# DigitalHourglass.net
KiCad netlist of a schematic drawn in EAGLE
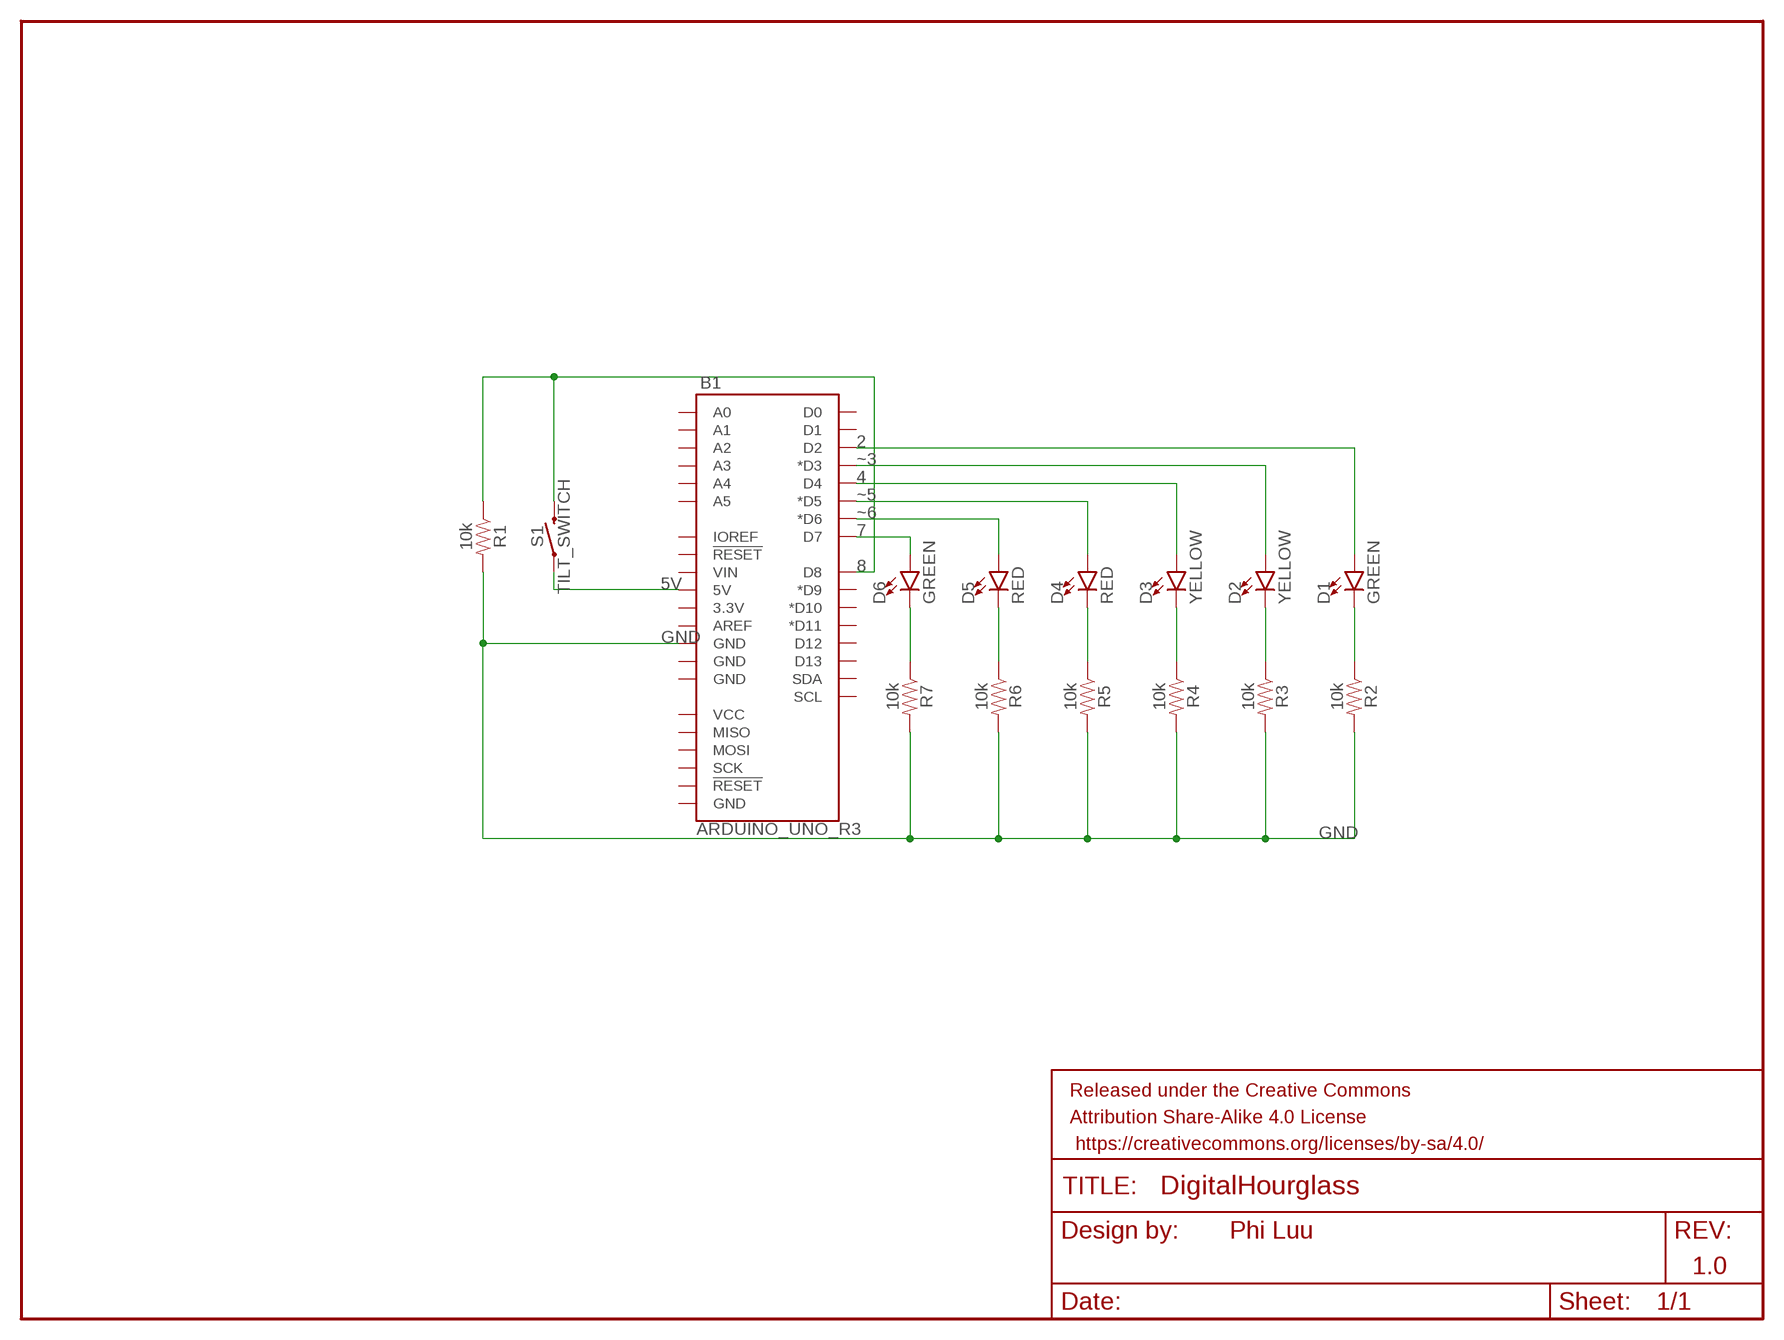
[diagram p0: schematic, sheet 1]

(export (version "E")
  (design (tool "Eeschema 10.0.6"))
  (components
    (comp (ref "B1")
      (value "ARDUINO_UNO_R3")
      (footprint "eagle-import:ARDUINO_R3")
      (libsource (lib "eagle-import") (part "ARDUINO_UNO_R3"))
    )
    (comp (ref "D1")
      (value "GREEN")
      (footprint "eagle-import:LED_5MM")
      (libsource (lib "eagle-import") (part "LED5MM"))
    )
    (comp (ref "D2")
      (value "YELLOW")
      (footprint "eagle-import:LED_5MM")
      (libsource (lib "eagle-import") (part "LED5MM"))
    )
    (comp (ref "D3")
      (value "YELLOW")
      (footprint "eagle-import:LED_5MM")
      (libsource (lib "eagle-import") (part "LED5MM"))
    )
    (comp (ref "D4")
      (value "RED")
      (footprint "eagle-import:LED_5MM")
      (libsource (lib "eagle-import") (part "LED5MM"))
    )
    (comp (ref "D5")
      (value "RED")
      (footprint "eagle-import:LED_5MM")
      (libsource (lib "eagle-import") (part "LED5MM"))
    )
    (comp (ref "D6")
      (value "GREEN")
      (footprint "eagle-import:LED_5MM")
      (libsource (lib "eagle-import") (part "LED5MM"))
    )
    (comp (ref "FRAME1")
      (value "FRAME-LETTER")
      (footprint "eagle-import:CREATIVE_COMMONS")
      (libsource (lib "eagle-import") (part "FRAME-LETTER"))
    )
    (comp (ref "R1")
      (value "10k")
      (footprint "eagle-import:AXIAL-0.3")
      (libsource (lib "eagle-import") (part "10KOHM-HORIZ-1/4W-5%"))
    )
    (comp (ref "R2")
      (value "10k")
      (footprint "eagle-import:AXIAL-0.3")
      (libsource (lib "eagle-import") (part "10KOHM-HORIZ-1/4W-5%"))
    )
    (comp (ref "R3")
      (value "10k")
      (footprint "eagle-import:AXIAL-0.3")
      (libsource (lib "eagle-import") (part "10KOHM-HORIZ-1/4W-5%"))
    )
    (comp (ref "R4")
      (value "10k")
      (footprint "eagle-import:AXIAL-0.3")
      (libsource (lib "eagle-import") (part "10KOHM-HORIZ-1/4W-5%"))
    )
    (comp (ref "R5")
      (value "10k")
      (footprint "eagle-import:AXIAL-0.3")
      (libsource (lib "eagle-import") (part "10KOHM-HORIZ-1/4W-5%"))
    )
    (comp (ref "R6")
      (value "10k")
      (footprint "eagle-import:AXIAL-0.3")
      (libsource (lib "eagle-import") (part "10KOHM-HORIZ-1/4W-5%"))
    )
    (comp (ref "R7")
      (value "10k")
      (footprint "eagle-import:AXIAL-0.3")
      (libsource (lib "eagle-import") (part "10KOHM-HORIZ-1/4W-5%"))
    )
    (comp (ref "S1")
      (value "TILT_SWITCH")
      (footprint "eagle-import:TACTILE_SWITCH_PTH_6.0MM")
      (libsource (lib "eagle-import") (part "MOMENTARY-SWITCH-SPST-PTH-6.0MM"))
    )
  )
  (nets
    (net (code "1") (name "/2") (class "Default")
      (node (ref "B1") (pin "D2") (pinfunction "D2_D2") (pintype "bidirectional"))
      (node (ref "D1") (pin "A") (pinfunction "A_A") (pintype "passive"))
    )
    (net (code "2") (name "/4") (class "Default")
      (node (ref "B1") (pin "D4") (pinfunction "D4_D4") (pintype "bidirectional"))
      (node (ref "D3") (pin "A") (pinfunction "A_A") (pintype "passive"))
    )
    (net (code "3") (name "/5V") (class "Default")
      (node (ref "B1") (pin "5V") (pinfunction "5V_5V") (pintype "bidirectional"))
      (node (ref "S1") (pin "1") (pinfunction "1_1") (pintype "passive"))
    )
    (net (code "4") (name "/7") (class "Default")
      (node (ref "B1") (pin "D7") (pinfunction "D7_D7") (pintype "bidirectional"))
      (node (ref "D6") (pin "A") (pinfunction "A_A") (pintype "passive"))
    )
    (net (code "5") (name "/8") (class "Default")
      (node (ref "B1") (pin "D8") (pinfunction "D8_D8") (pintype "bidirectional"))
      (node (ref "R1") (pin "P$1") (pinfunction "1_P$1") (pintype "passive"))
      (node (ref "S1") (pin "3") (pinfunction "2_3") (pintype "passive"))
    )
    (net (code "6") (name "/GND") (class "Default")
      (node (ref "B1") (pin "GND@4") (pinfunction "GND_GND@4") (pintype "bidirectional"))
      (node (ref "R1") (pin "P$2") (pinfunction "2_P$2") (pintype "passive"))
      (node (ref "R2") (pin "P$2") (pinfunction "2_P$2") (pintype "passive"))
      (node (ref "R3") (pin "P$2") (pinfunction "2_P$2") (pintype "passive"))
      (node (ref "R4") (pin "P$2") (pinfunction "2_P$2") (pintype "passive"))
      (node (ref "R5") (pin "P$2") (pinfunction "2_P$2") (pintype "passive"))
      (node (ref "R6") (pin "P$2") (pinfunction "2_P$2") (pintype "passive"))
      (node (ref "R7") (pin "P$2") (pinfunction "2_P$2") (pintype "passive"))
    )
    (net (code "7") (name "/~{3}") (class "Default")
      (node (ref "B1") (pin "D3") (pinfunction "*D3_D3") (pintype "bidirectional"))
      (node (ref "D2") (pin "A") (pinfunction "A_A") (pintype "passive"))
    )
    (net (code "8") (name "/~{5}") (class "Default")
      (node (ref "B1") (pin "D5") (pinfunction "*D5_D5") (pintype "bidirectional"))
      (node (ref "D4") (pin "A") (pinfunction "A_A") (pintype "passive"))
    )
    (net (code "9") (name "/~{6}") (class "Default")
      (node (ref "B1") (pin "D6") (pinfunction "*D6_D6") (pintype "bidirectional"))
      (node (ref "D5") (pin "A") (pinfunction "A_A") (pintype "passive"))
    )
    (net (code "10") (name "Net-(D1-C)") (class "Default")
      (node (ref "D1") (pin "K") (pinfunction "C_K") (pintype "passive"))
      (node (ref "R2") (pin "P$1") (pinfunction "1_P$1") (pintype "passive"))
    )
    (net (code "11") (name "Net-(D2-C)") (class "Default")
      (node (ref "D2") (pin "K") (pinfunction "C_K") (pintype "passive"))
      (node (ref "R3") (pin "P$1") (pinfunction "1_P$1") (pintype "passive"))
    )
    (net (code "12") (name "Net-(D3-C)") (class "Default")
      (node (ref "D3") (pin "K") (pinfunction "C_K") (pintype "passive"))
      (node (ref "R4") (pin "P$1") (pinfunction "1_P$1") (pintype "passive"))
    )
    (net (code "13") (name "Net-(D4-C)") (class "Default")
      (node (ref "D4") (pin "K") (pinfunction "C_K") (pintype "passive"))
      (node (ref "R5") (pin "P$1") (pinfunction "1_P$1") (pintype "passive"))
    )
    (net (code "14") (name "Net-(D5-C)") (class "Default")
      (node (ref "D5") (pin "K") (pinfunction "C_K") (pintype "passive"))
      (node (ref "R6") (pin "P$1") (pinfunction "1_P$1") (pintype "passive"))
    )
    (net (code "15") (name "Net-(D6-C)") (class "Default")
      (node (ref "D6") (pin "K") (pinfunction "C_K") (pintype "passive"))
      (node (ref "R7") (pin "P$1") (pinfunction "1_P$1") (pintype "passive"))
    )
    (net (code "16") (name "unconnected-(B1-*D9-PadD9)") (class "Default")
      (node (ref "B1") (pin "D9") (pinfunction "*D9_D9") (pintype "bidirectional"))
    )
    (net (code "17") (name "unconnected-(B1-*D10-PadD10)") (class "Default")
      (node (ref "B1") (pin "D10") (pinfunction "*D10_D10") (pintype "bidirectional"))
    )
    (net (code "18") (name "unconnected-(B1-*D11-PadD11)") (class "Default")
      (node (ref "B1") (pin "D11") (pinfunction "*D11_D11") (pintype "bidirectional"))
    )
    (net (code "19") (name "unconnected-(B1-GND-PadGND@1)") (class "Default")
      (node (ref "B1") (pin "GND@1") (pinfunction "GND_GND@1") (pintype "bidirectional"))
    )
    (net (code "20") (name "unconnected-(B1-GND-PadGND@2)") (class "Default")
      (node (ref "B1") (pin "GND@2") (pinfunction "GND_GND@2") (pintype "bidirectional"))
    )
    (net (code "21") (name "unconnected-(B1-GND-PadGND@3)") (class "Default")
      (node (ref "B1") (pin "GND@3") (pinfunction "GND_GND@3") (pintype "bidirectional"))
    )
    (net (code "22") (name "unconnected-(B1-Pad3.3V)") (class "Default")
      (node (ref "B1") (pin "3.3V") (pinfunction "3.3V_3.3V") (pintype "bidirectional"))
    )
    (net (code "23") (name "unconnected-(B1-PadA0)") (class "Default")
      (node (ref "B1") (pin "A0") (pinfunction "A0_A0") (pintype "bidirectional"))
    )
    (net (code "24") (name "unconnected-(B1-PadA1)") (class "Default")
      (node (ref "B1") (pin "A1") (pinfunction "A1_A1") (pintype "bidirectional"))
    )
    (net (code "25") (name "unconnected-(B1-PadA2)") (class "Default")
      (node (ref "B1") (pin "A2") (pinfunction "A2_A2") (pintype "bidirectional"))
    )
    (net (code "26") (name "unconnected-(B1-PadA3)") (class "Default")
      (node (ref "B1") (pin "A3") (pinfunction "A3_A3") (pintype "bidirectional"))
    )
    (net (code "27") (name "unconnected-(B1-PadA4)") (class "Default")
      (node (ref "B1") (pin "A4") (pinfunction "A4_A4") (pintype "bidirectional"))
    )
    (net (code "28") (name "unconnected-(B1-PadA5)") (class "Default")
      (node (ref "B1") (pin "A5") (pinfunction "A5_A5") (pintype "bidirectional"))
    )
    (net (code "29") (name "unconnected-(B1-PadAREF)") (class "Default")
      (node (ref "B1") (pin "AREF") (pinfunction "AREF_AREF") (pintype "bidirectional"))
    )
    (net (code "30") (name "unconnected-(B1-PadD0)") (class "Default")
      (node (ref "B1") (pin "D0") (pinfunction "D0_D0") (pintype "bidirectional"))
    )
    (net (code "31") (name "unconnected-(B1-PadD1)") (class "Default")
      (node (ref "B1") (pin "D1") (pinfunction "D1_D1") (pintype "bidirectional"))
    )
    (net (code "32") (name "unconnected-(B1-PadD12)") (class "Default")
      (node (ref "B1") (pin "D12") (pinfunction "D12_D12") (pintype "bidirectional"))
    )
    (net (code "33") (name "unconnected-(B1-PadD13)") (class "Default")
      (node (ref "B1") (pin "D13") (pinfunction "D13_D13") (pintype "bidirectional"))
    )
    (net (code "34") (name "unconnected-(B1-PadIOREF)") (class "Default")
      (node (ref "B1") (pin "IOREF") (pinfunction "IOREF_IOREF") (pintype "bidirectional"))
    )
    (net (code "35") (name "unconnected-(B1-PadMISO)") (class "Default")
      (node (ref "B1") (pin "MISO") (pinfunction "MISO_MISO") (pintype "bidirectional"))
    )
    (net (code "36") (name "unconnected-(B1-PadMOSI)") (class "Default")
      (node (ref "B1") (pin "MOSI") (pinfunction "MOSI_MOSI") (pintype "bidirectional"))
    )
    (net (code "37") (name "unconnected-(B1-PadSCK)") (class "Default")
      (node (ref "B1") (pin "SCK") (pinfunction "SCK_SCK") (pintype "bidirectional"))
    )
    (net (code "38") (name "unconnected-(B1-PadSCL)") (class "Default")
      (node (ref "B1") (pin "SCL") (pinfunction "SCL_SCL") (pintype "bidirectional"))
    )
    (net (code "39") (name "unconnected-(B1-PadSDA)") (class "Default")
      (node (ref "B1") (pin "SDA") (pinfunction "SDA_SDA") (pintype "bidirectional"))
    )
    (net (code "40") (name "unconnected-(B1-PadVCC)") (class "Default")
      (node (ref "B1") (pin "VCC") (pinfunction "VCC_VCC") (pintype "bidirectional"))
    )
    (net (code "41") (name "unconnected-(B1-PadVIN)") (class "Default")
      (node (ref "B1") (pin "VIN") (pinfunction "VIN_VIN") (pintype "bidirectional"))
    )
    (net (code "42") (name "unconnected-(B1-~{RESET}-PadRESET@1)") (class "Default")
      (node (ref "B1") (pin "RESET@1") (pinfunction "~{RESET}_RESET@1") (pintype "bidirectional"))
    )
    (net (code "43") (name "unconnected-(B1-~{RESET}-PadRESET@2)") (class "Default")
      (node (ref "B1") (pin "RESET@2") (pinfunction "~{RESET}_RESET@2") (pintype "bidirectional"))
    )
  )
)
